# quasi_nano_led_2sided.net
KiCad netlist of a schematic drawn in EAGLE
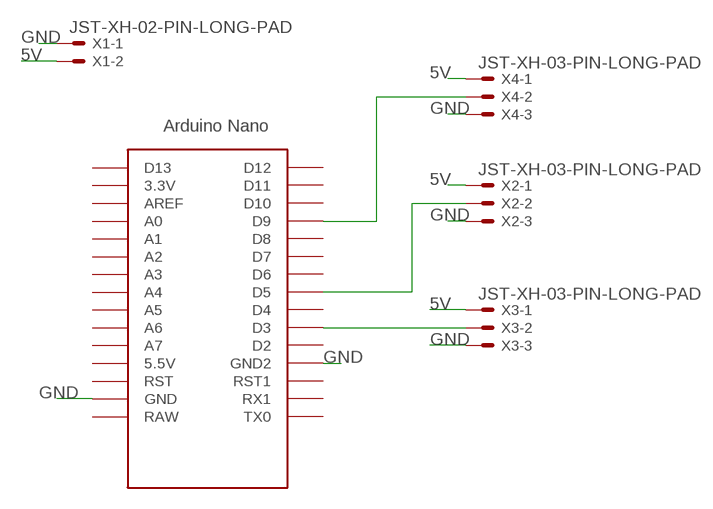
[diagram p0: schematic, sheet 1]

(export (version "E")
  (design (tool "Eeschema 10.0.6"))
  (components
    (comp (ref "U$1")
      (value "NANO")
      (footprint "eagle-import:NANO")
      (libsource (lib "eagle-import") (part "NANO"))
    )
    (comp (ref "X1")
      (value "JST-XH-02-PIN-LONG-PAD")
      (footprint "eagle-import:JST-XH-02-PACKAGE-LONG-PAD")
      (libsource (lib "eagle-import") (part "JST-XH-02-PIN-LONG-PAD"))
    )
    (comp (ref "X2")
      (value "JST-XH-03-PIN-LONG-PAD")
      (footprint "eagle-import:JST-XH-03-PACKAGE-LONG-PAD")
      (libsource (lib "eagle-import") (part "JST-XH-03-PIN-LONG-PAD"))
    )
    (comp (ref "X3")
      (value "JST-XH-03-PIN-LONG-PAD")
      (footprint "eagle-import:JST-XH-03-PACKAGE-LONG-PAD")
      (libsource (lib "eagle-import") (part "JST-XH-03-PIN-LONG-PAD"))
    )
    (comp (ref "X4")
      (value "JST-XH-03-PIN-LONG-PAD")
      (footprint "eagle-import:JST-XH-03-PACKAGE-LONG-PAD")
      (libsource (lib "eagle-import") (part "JST-XH-03-PIN-LONG-PAD"))
    )
  )
  (nets
    (net (code "1") (name "/5V") (class "Default")
      (node (ref "X1") (pin "2") (pinfunction "S_2") (pintype "passive"))
      (node (ref "X2") (pin "1") (pinfunction "S_1") (pintype "passive"))
      (node (ref "X3") (pin "1") (pinfunction "S_1") (pintype "passive"))
      (node (ref "X4") (pin "1") (pinfunction "S_1") (pintype "passive"))
    )
    (net (code "2") (name "/GND") (class "Default")
      (node (ref "U$1") (pin "GND") (pinfunction "GND_GND") (pintype "bidirectional"))
      (node (ref "U$1") (pin "GND1") (pinfunction "GND2_GND1") (pintype "bidirectional"))
      (node (ref "X1") (pin "1") (pinfunction "S_1") (pintype "passive"))
      (node (ref "X2") (pin "3") (pinfunction "S_3") (pintype "passive"))
      (node (ref "X3") (pin "3") (pinfunction "S_3") (pintype "passive"))
      (node (ref "X4") (pin "3") (pinfunction "S_3") (pintype "passive"))
    )
    (net (code "3") (name "Net-(X2B-S)") (class "Default")
      (node (ref "U$1") (pin "D5") (pinfunction "D5_D5") (pintype "bidirectional"))
      (node (ref "X2") (pin "2") (pinfunction "S_2") (pintype "passive"))
    )
    (net (code "4") (name "Net-(X3B-S)") (class "Default")
      (node (ref "U$1") (pin "D3") (pinfunction "D3_D3") (pintype "bidirectional"))
      (node (ref "X3") (pin "2") (pinfunction "S_2") (pintype "passive"))
    )
    (net (code "5") (name "Net-(X4B-S)") (class "Default")
      (node (ref "U$1") (pin "D9") (pinfunction "D9_D9") (pintype "bidirectional"))
      (node (ref "X4") (pin "2") (pinfunction "S_2") (pintype "passive"))
    )
    (net (code "6") (name "unconnected-(U$1-5.5V-Pad5V)") (class "Default")
      (node (ref "U$1") (pin "5V") (pinfunction "5.5V_5V") (pintype "bidirectional"))
    )
    (net (code "7") (name "unconnected-(U$1-Pad3.3V)") (class "Default")
      (node (ref "U$1") (pin "3.3V") (pinfunction "3.3V_3.3V") (pintype "bidirectional"))
    )
    (net (code "8") (name "unconnected-(U$1-PadA0)") (class "Default")
      (node (ref "U$1") (pin "A0") (pinfunction "A0_A0") (pintype "bidirectional"))
    )
    (net (code "9") (name "unconnected-(U$1-PadA1)") (class "Default")
      (node (ref "U$1") (pin "A1") (pinfunction "A1_A1") (pintype "bidirectional"))
    )
    (net (code "10") (name "unconnected-(U$1-PadA2)") (class "Default")
      (node (ref "U$1") (pin "A2") (pinfunction "A2_A2") (pintype "bidirectional"))
    )
    (net (code "11") (name "unconnected-(U$1-PadA3)") (class "Default")
      (node (ref "U$1") (pin "A3") (pinfunction "A3_A3") (pintype "bidirectional"))
    )
    (net (code "12") (name "unconnected-(U$1-PadA4)") (class "Default")
      (node (ref "U$1") (pin "A4") (pinfunction "A4_A4") (pintype "bidirectional"))
    )
    (net (code "13") (name "unconnected-(U$1-PadA5)") (class "Default")
      (node (ref "U$1") (pin "A5") (pinfunction "A5_A5") (pintype "bidirectional"))
    )
    (net (code "14") (name "unconnected-(U$1-PadA6)") (class "Default")
      (node (ref "U$1") (pin "A6") (pinfunction "A6_A6") (pintype "bidirectional"))
    )
    (net (code "15") (name "unconnected-(U$1-PadA7)") (class "Default")
      (node (ref "U$1") (pin "A7") (pinfunction "A7_A7") (pintype "bidirectional"))
    )
    (net (code "16") (name "unconnected-(U$1-PadAREF)") (class "Default")
      (node (ref "U$1") (pin "AREF") (pinfunction "AREF_AREF") (pintype "bidirectional"))
    )
    (net (code "17") (name "unconnected-(U$1-PadD2)") (class "Default")
      (node (ref "U$1") (pin "D2") (pinfunction "D2_D2") (pintype "bidirectional"))
    )
    (net (code "18") (name "unconnected-(U$1-PadD4)") (class "Default")
      (node (ref "U$1") (pin "D4") (pinfunction "D4_D4") (pintype "bidirectional"))
    )
    (net (code "19") (name "unconnected-(U$1-PadD6)") (class "Default")
      (node (ref "U$1") (pin "D6") (pinfunction "D6_D6") (pintype "bidirectional"))
    )
    (net (code "20") (name "unconnected-(U$1-PadD7)") (class "Default")
      (node (ref "U$1") (pin "D7") (pinfunction "D7_D7") (pintype "bidirectional"))
    )
    (net (code "21") (name "unconnected-(U$1-PadD8)") (class "Default")
      (node (ref "U$1") (pin "D8") (pinfunction "D8_D8") (pintype "bidirectional"))
    )
    (net (code "22") (name "unconnected-(U$1-PadD10)") (class "Default")
      (node (ref "U$1") (pin "D10") (pinfunction "D10_D10") (pintype "bidirectional"))
    )
    (net (code "23") (name "unconnected-(U$1-PadD11)") (class "Default")
      (node (ref "U$1") (pin "D11") (pinfunction "D11_D11") (pintype "bidirectional"))
    )
    (net (code "24") (name "unconnected-(U$1-PadD12)") (class "Default")
      (node (ref "U$1") (pin "D12") (pinfunction "D12_D12") (pintype "bidirectional"))
    )
    (net (code "25") (name "unconnected-(U$1-PadD13)") (class "Default")
      (node (ref "U$1") (pin "D13") (pinfunction "D13_D13") (pintype "bidirectional"))
    )
    (net (code "26") (name "unconnected-(U$1-PadICSP1)") (class "Default")
      (node (ref "U$1") (pin "ICSP1") (pinfunction "ICSP1_ICSP1") (pintype "bidirectional"))
    )
    (net (code "27") (name "unconnected-(U$1-PadICSP2)") (class "Default")
      (node (ref "U$1") (pin "ICSP2") (pinfunction "ICSP2_ICSP2") (pintype "bidirectional"))
    )
    (net (code "28") (name "unconnected-(U$1-PadICSP3)") (class "Default")
      (node (ref "U$1") (pin "ICSP3") (pinfunction "ICSP3_ICSP3") (pintype "bidirectional"))
    )
    (net (code "29") (name "unconnected-(U$1-PadICSP4)") (class "Default")
      (node (ref "U$1") (pin "ICSP4") (pinfunction "ICSP4_ICSP4") (pintype "bidirectional"))
    )
    (net (code "30") (name "unconnected-(U$1-PadICSP5)") (class "Default")
      (node (ref "U$1") (pin "ICSP5") (pinfunction "ICSP5_ICSP5") (pintype "bidirectional"))
    )
    (net (code "31") (name "unconnected-(U$1-PadICSP6)") (class "Default")
      (node (ref "U$1") (pin "ICSP6") (pinfunction "ICSP6_ICSP6") (pintype "bidirectional"))
    )
    (net (code "32") (name "unconnected-(U$1-PadRAW)") (class "Default")
      (node (ref "U$1") (pin "RAW") (pinfunction "RAW_RAW") (pintype "bidirectional"))
    )
    (net (code "33") (name "unconnected-(U$1-PadRST)") (class "Default")
      (node (ref "U$1") (pin "RST") (pinfunction "RST_RST") (pintype "bidirectional"))
    )
    (net (code "34") (name "unconnected-(U$1-PadRST1)") (class "Default")
      (node (ref "U$1") (pin "RST1") (pinfunction "RST1_RST1") (pintype "bidirectional"))
    )
    (net (code "35") (name "unconnected-(U$1-PadRX1)") (class "Default")
      (node (ref "U$1") (pin "RX1") (pinfunction "RX1_RX1") (pintype "bidirectional"))
    )
    (net (code "36") (name "unconnected-(U$1-PadTX0)") (class "Default")
      (node (ref "U$1") (pin "TX0") (pinfunction "TX0_TX0") (pintype "bidirectional"))
    )
  )
)
